# headstage.net
KiCad netlist of a schematic drawn in EAGLE
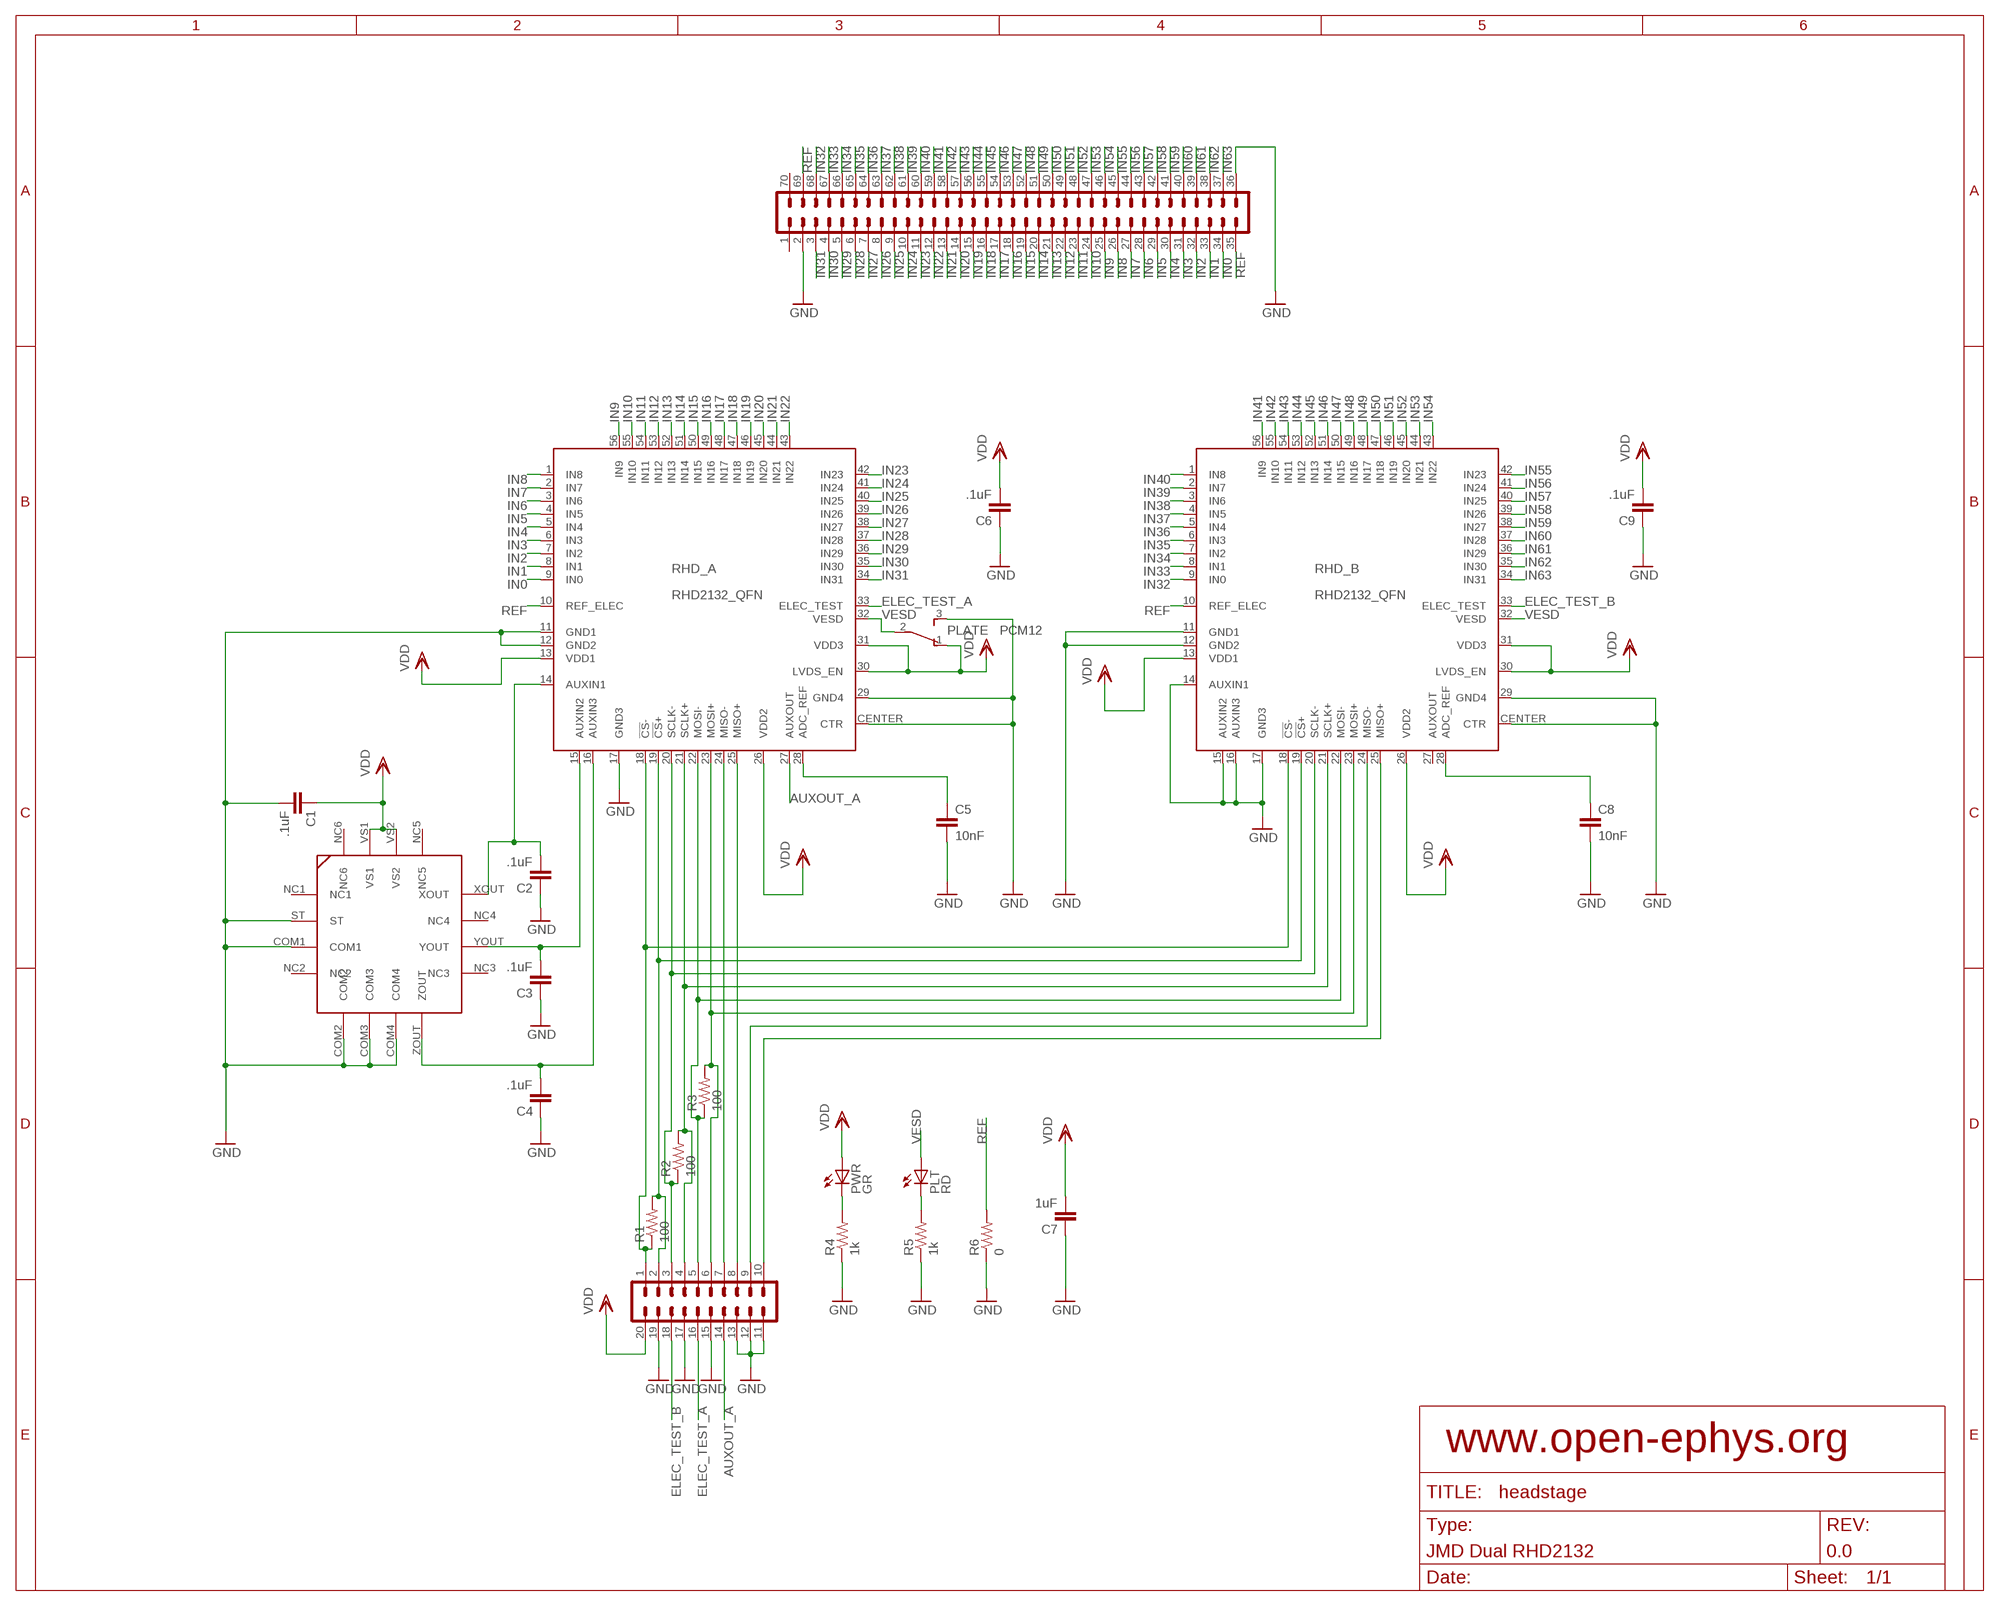
[diagram p0: schematic, sheet 1]

(export (version "E")
  (design (tool "Eeschema 10.0.6"))
  (components
    (comp (ref "AIN")
      (value "JMD70")
      (footprint "eagle-import:JMD70")
      (libsource (lib "eagle-import") (part "PINHD-2X35_JMD70"))
    )
    (comp (ref "C1")
      (value ".1uF")
      (footprint "eagle-import:0402")
      (libsource (lib "eagle-import") (part "C_0402"))
    )
    (comp (ref "C2")
      (value ".1uF")
      (footprint "eagle-import:0402")
      (libsource (lib "eagle-import") (part "C_0402"))
    )
    (comp (ref "C3")
      (value ".1uF")
      (footprint "eagle-import:0402")
      (libsource (lib "eagle-import") (part "C_0402"))
    )
    (comp (ref "C4")
      (value ".1uF")
      (footprint "eagle-import:0402")
      (libsource (lib "eagle-import") (part "C_0402"))
    )
    (comp (ref "C5")
      (value "10nF")
      (footprint "eagle-import:0402")
      (libsource (lib "eagle-import") (part "C_0402"))
    )
    (comp (ref "C6")
      (value ".1uF")
      (footprint "eagle-import:0603")
      (libsource (lib "eagle-import") (part "C_0603"))
    )
    (comp (ref "C7")
      (value "1uF")
      (footprint "eagle-import:0603")
      (libsource (lib "eagle-import") (part "C_0603"))
    )
    (comp (ref "C8")
      (value "10nF")
      (footprint "eagle-import:0402")
      (libsource (lib "eagle-import") (part "C_0402"))
    )
    (comp (ref "C9")
      (value ".1uF")
      (footprint "eagle-import:0603")
      (libsource (lib "eagle-import") (part "C_0603"))
    )
    (comp (ref "OUT")
      (value "JMD")
      (footprint "eagle-import:JMD20-RA")
      (libsource (lib "eagle-import") (part "PINHD-2X10_JMD-RA"))
    )
    (comp (ref "PLATE")
      (value "PCM12")
      (footprint "eagle-import:PCM12")
      (libsource (lib "eagle-import") (part "SPDT_PCM12"))
    )
    (comp (ref "PLT")
      (value "RD")
      (footprint "eagle-import:CHIP-LED0603")
      (libsource (lib "eagle-import") (part "LED_0603"))
    )
    (comp (ref "PWR")
      (value "GR")
      (footprint "eagle-import:CHIP-LED0603")
      (libsource (lib "eagle-import") (part "LED_0603"))
    )
    (comp (ref "R1")
      (value "100")
      (footprint "eagle-import:0402")
      (libsource (lib "eagle-import") (part "R_0402"))
    )
    (comp (ref "R2")
      (value "100")
      (footprint "eagle-import:0402")
      (libsource (lib "eagle-import") (part "R_0402"))
    )
    (comp (ref "R3")
      (value "100")
      (footprint "eagle-import:0402")
      (libsource (lib "eagle-import") (part "R_0402"))
    )
    (comp (ref "R4")
      (value "1k")
      (footprint "eagle-import:0402")
      (libsource (lib "eagle-import") (part "R_0402"))
    )
    (comp (ref "R5")
      (value "1k")
      (footprint "eagle-import:0402")
      (libsource (lib "eagle-import") (part "R_0402"))
    )
    (comp (ref "R6")
      (value "0")
      (footprint "eagle-import:0402")
      (libsource (lib "eagle-import") (part "R_0402"))
    )
    (comp (ref "RHD_A")
      (value "RHD2132_QFN")
      (footprint "eagle-import:QFN56_8_X_8_LARGE")
      (libsource (lib "eagle-import") (part "RHD2132_QFN"))
    )
    (comp (ref "RHD_B")
      (value "RHD2132_QFN")
      (footprint "eagle-import:QFN56_8_X_8_LARGE")
      (libsource (lib "eagle-import") (part "RHD2132_QFN"))
    )
    (comp (ref "U1")
      (value "ADXL335")
      (footprint "eagle-import:ADXL335")
      (libsource (lib "eagle-import") (part "ADXL335"))
    )
  )
  (nets
    (net (code "1") (name "/AUXOUT_A") (class "Default")
      (node (ref "OUT") (pin "14") (pinfunction "14_14") (pintype "bidirectional"))
      (node (ref "RHD_A") (pin "27") (pinfunction "AUXOUT_27") (pintype "tri_state"))
    )
    (net (code "2") (name "/ELEC_TEST_A") (class "Default")
      (node (ref "OUT") (pin "16") (pinfunction "16_16") (pintype "bidirectional"))
      (node (ref "RHD_A") (pin "33") (pinfunction "ELEC_TEST_33") (pintype "input"))
    )
    (net (code "3") (name "/ELEC_TEST_B") (class "Default")
      (node (ref "OUT") (pin "18") (pinfunction "18_18") (pintype "bidirectional"))
      (node (ref "RHD_B") (pin "33") (pinfunction "ELEC_TEST_33") (pintype "input"))
    )
    (net (code "4") (name "/IN0") (class "Default")
      (node (ref "AIN") (pin "34") (pinfunction "34_34") (pintype "bidirectional"))
      (node (ref "RHD_A") (pin "9") (pinfunction "IN0_9") (pintype "input"))
    )
    (net (code "5") (name "/IN1") (class "Default")
      (node (ref "AIN") (pin "33") (pinfunction "33_33") (pintype "bidirectional"))
      (node (ref "RHD_A") (pin "8") (pinfunction "IN1_8") (pintype "input"))
    )
    (net (code "6") (name "/IN2") (class "Default")
      (node (ref "AIN") (pin "32") (pinfunction "32_32") (pintype "bidirectional"))
      (node (ref "RHD_A") (pin "7") (pinfunction "IN2_7") (pintype "input"))
    )
    (net (code "7") (name "/IN3") (class "Default")
      (node (ref "AIN") (pin "31") (pinfunction "31_31") (pintype "bidirectional"))
      (node (ref "RHD_A") (pin "6") (pinfunction "IN3_6") (pintype "input"))
    )
    (net (code "8") (name "/IN4") (class "Default")
      (node (ref "AIN") (pin "30") (pinfunction "30_30") (pintype "bidirectional"))
      (node (ref "RHD_A") (pin "5") (pinfunction "IN4_5") (pintype "input"))
    )
    (net (code "9") (name "/IN5") (class "Default")
      (node (ref "AIN") (pin "29") (pinfunction "29_29") (pintype "bidirectional"))
      (node (ref "RHD_A") (pin "4") (pinfunction "IN5_4") (pintype "input"))
    )
    (net (code "10") (name "/IN6") (class "Default")
      (node (ref "AIN") (pin "28") (pinfunction "28_28") (pintype "bidirectional"))
      (node (ref "RHD_A") (pin "3") (pinfunction "IN6_3") (pintype "input"))
    )
    (net (code "11") (name "/IN7") (class "Default")
      (node (ref "AIN") (pin "27") (pinfunction "27_27") (pintype "bidirectional"))
      (node (ref "RHD_A") (pin "2") (pinfunction "IN7_2") (pintype "input"))
    )
    (net (code "12") (name "/IN8") (class "Default")
      (node (ref "AIN") (pin "26") (pinfunction "26_26") (pintype "bidirectional"))
      (node (ref "RHD_A") (pin "1") (pinfunction "IN8_1") (pintype "input"))
    )
    (net (code "13") (name "/IN9") (class "Default")
      (node (ref "AIN") (pin "25") (pinfunction "25_25") (pintype "bidirectional"))
      (node (ref "RHD_A") (pin "56") (pinfunction "IN9_56") (pintype "input"))
    )
    (net (code "14") (name "/IN10") (class "Default")
      (node (ref "AIN") (pin "24") (pinfunction "24_24") (pintype "bidirectional"))
      (node (ref "RHD_A") (pin "55") (pinfunction "IN10_55") (pintype "input"))
    )
    (net (code "15") (name "/IN11") (class "Default")
      (node (ref "AIN") (pin "23") (pinfunction "23_23") (pintype "bidirectional"))
      (node (ref "RHD_A") (pin "54") (pinfunction "IN11_54") (pintype "input"))
    )
    (net (code "16") (name "/IN12") (class "Default")
      (node (ref "AIN") (pin "22") (pinfunction "22_22") (pintype "bidirectional"))
      (node (ref "RHD_A") (pin "53") (pinfunction "IN12_53") (pintype "input"))
    )
    (net (code "17") (name "/IN13") (class "Default")
      (node (ref "AIN") (pin "21") (pinfunction "21_21") (pintype "bidirectional"))
      (node (ref "RHD_A") (pin "52") (pinfunction "IN13_52") (pintype "input"))
    )
    (net (code "18") (name "/IN14") (class "Default")
      (node (ref "AIN") (pin "20") (pinfunction "20_20") (pintype "bidirectional"))
      (node (ref "RHD_A") (pin "51") (pinfunction "IN14_51") (pintype "input"))
    )
    (net (code "19") (name "/IN15") (class "Default")
      (node (ref "AIN") (pin "19") (pinfunction "19_19") (pintype "bidirectional"))
      (node (ref "RHD_A") (pin "50") (pinfunction "IN15_50") (pintype "input"))
    )
    (net (code "20") (name "/IN16") (class "Default")
      (node (ref "AIN") (pin "18") (pinfunction "18_18") (pintype "bidirectional"))
      (node (ref "RHD_A") (pin "49") (pinfunction "IN16_49") (pintype "input"))
    )
    (net (code "21") (name "/IN17") (class "Default")
      (node (ref "AIN") (pin "17") (pinfunction "17_17") (pintype "bidirectional"))
      (node (ref "RHD_A") (pin "48") (pinfunction "IN17_48") (pintype "input"))
    )
    (net (code "22") (name "/IN18") (class "Default")
      (node (ref "AIN") (pin "16") (pinfunction "16_16") (pintype "bidirectional"))
      (node (ref "RHD_A") (pin "47") (pinfunction "IN18_47") (pintype "input"))
    )
    (net (code "23") (name "/IN19") (class "Default")
      (node (ref "AIN") (pin "15") (pinfunction "15_15") (pintype "bidirectional"))
      (node (ref "RHD_A") (pin "46") (pinfunction "IN19_46") (pintype "input"))
    )
    (net (code "24") (name "/IN20") (class "Default")
      (node (ref "AIN") (pin "14") (pinfunction "14_14") (pintype "bidirectional"))
      (node (ref "RHD_A") (pin "45") (pinfunction "IN20_45") (pintype "input"))
    )
    (net (code "25") (name "/IN21") (class "Default")
      (node (ref "AIN") (pin "13") (pinfunction "13_13") (pintype "bidirectional"))
      (node (ref "RHD_A") (pin "44") (pinfunction "IN21_44") (pintype "input"))
    )
    (net (code "26") (name "/IN22") (class "Default")
      (node (ref "AIN") (pin "12") (pinfunction "12_12") (pintype "bidirectional"))
      (node (ref "RHD_A") (pin "43") (pinfunction "IN22_43") (pintype "input"))
    )
    (net (code "27") (name "/IN23") (class "Default")
      (node (ref "AIN") (pin "11") (pinfunction "11_11") (pintype "bidirectional"))
      (node (ref "RHD_A") (pin "42") (pinfunction "IN23_42") (pintype "input"))
    )
    (net (code "28") (name "/IN24") (class "Default")
      (node (ref "AIN") (pin "10") (pinfunction "10_10") (pintype "bidirectional"))
      (node (ref "RHD_A") (pin "41") (pinfunction "IN24_41") (pintype "input"))
    )
    (net (code "29") (name "/IN25") (class "Default")
      (node (ref "AIN") (pin "9") (pinfunction "9_9") (pintype "bidirectional"))
      (node (ref "RHD_A") (pin "40") (pinfunction "IN25_40") (pintype "input"))
    )
    (net (code "30") (name "/IN26") (class "Default")
      (node (ref "AIN") (pin "8") (pinfunction "8_8") (pintype "bidirectional"))
      (node (ref "RHD_A") (pin "39") (pinfunction "IN26_39") (pintype "input"))
    )
    (net (code "31") (name "/IN27") (class "Default")
      (node (ref "AIN") (pin "7") (pinfunction "7_7") (pintype "bidirectional"))
      (node (ref "RHD_A") (pin "38") (pinfunction "IN27_38") (pintype "input"))
    )
    (net (code "32") (name "/IN28") (class "Default")
      (node (ref "AIN") (pin "6") (pinfunction "6_6") (pintype "bidirectional"))
      (node (ref "RHD_A") (pin "37") (pinfunction "IN28_37") (pintype "input"))
    )
    (net (code "33") (name "/IN29") (class "Default")
      (node (ref "AIN") (pin "5") (pinfunction "5_5") (pintype "bidirectional"))
      (node (ref "RHD_A") (pin "36") (pinfunction "IN29_36") (pintype "input"))
    )
    (net (code "34") (name "/IN30") (class "Default")
      (node (ref "AIN") (pin "4") (pinfunction "4_4") (pintype "bidirectional"))
      (node (ref "RHD_A") (pin "35") (pinfunction "IN30_35") (pintype "input"))
    )
    (net (code "35") (name "/IN31") (class "Default")
      (node (ref "AIN") (pin "3") (pinfunction "3_3") (pintype "bidirectional"))
      (node (ref "RHD_A") (pin "34") (pinfunction "IN31_34") (pintype "input"))
    )
    (net (code "36") (name "/IN32") (class "Default")
      (node (ref "AIN") (pin "68") (pinfunction "68_68") (pintype "bidirectional"))
      (node (ref "RHD_B") (pin "9") (pinfunction "IN0_9") (pintype "input"))
    )
    (net (code "37") (name "/IN33") (class "Default")
      (node (ref "AIN") (pin "67") (pinfunction "67_67") (pintype "bidirectional"))
      (node (ref "RHD_B") (pin "8") (pinfunction "IN1_8") (pintype "input"))
    )
    (net (code "38") (name "/IN34") (class "Default")
      (node (ref "AIN") (pin "66") (pinfunction "66_66") (pintype "bidirectional"))
      (node (ref "RHD_B") (pin "7") (pinfunction "IN2_7") (pintype "input"))
    )
    (net (code "39") (name "/IN35") (class "Default")
      (node (ref "AIN") (pin "65") (pinfunction "65_65") (pintype "bidirectional"))
      (node (ref "RHD_B") (pin "6") (pinfunction "IN3_6") (pintype "input"))
    )
    (net (code "40") (name "/IN36") (class "Default")
      (node (ref "AIN") (pin "64") (pinfunction "64_64") (pintype "bidirectional"))
      (node (ref "RHD_B") (pin "5") (pinfunction "IN4_5") (pintype "input"))
    )
    (net (code "41") (name "/IN37") (class "Default")
      (node (ref "AIN") (pin "63") (pinfunction "63_63") (pintype "bidirectional"))
      (node (ref "RHD_B") (pin "4") (pinfunction "IN5_4") (pintype "input"))
    )
    (net (code "42") (name "/IN38") (class "Default")
      (node (ref "AIN") (pin "62") (pinfunction "62_62") (pintype "bidirectional"))
      (node (ref "RHD_B") (pin "3") (pinfunction "IN6_3") (pintype "input"))
    )
    (net (code "43") (name "/IN39") (class "Default")
      (node (ref "AIN") (pin "61") (pinfunction "61_61") (pintype "bidirectional"))
      (node (ref "RHD_B") (pin "2") (pinfunction "IN7_2") (pintype "input"))
    )
    (net (code "44") (name "/IN40") (class "Default")
      (node (ref "AIN") (pin "60") (pinfunction "60_60") (pintype "bidirectional"))
      (node (ref "RHD_B") (pin "1") (pinfunction "IN8_1") (pintype "input"))
    )
    (net (code "45") (name "/IN41") (class "Default")
      (node (ref "AIN") (pin "59") (pinfunction "59_59") (pintype "bidirectional"))
      (node (ref "RHD_B") (pin "56") (pinfunction "IN9_56") (pintype "input"))
    )
    (net (code "46") (name "/IN42") (class "Default")
      (node (ref "AIN") (pin "58") (pinfunction "58_58") (pintype "bidirectional"))
      (node (ref "RHD_B") (pin "55") (pinfunction "IN10_55") (pintype "input"))
    )
    (net (code "47") (name "/IN43") (class "Default")
      (node (ref "AIN") (pin "57") (pinfunction "57_57") (pintype "bidirectional"))
      (node (ref "RHD_B") (pin "54") (pinfunction "IN11_54") (pintype "input"))
    )
    (net (code "48") (name "/IN44") (class "Default")
      (node (ref "AIN") (pin "56") (pinfunction "56_56") (pintype "bidirectional"))
      (node (ref "RHD_B") (pin "53") (pinfunction "IN12_53") (pintype "input"))
    )
    (net (code "49") (name "/IN45") (class "Default")
      (node (ref "AIN") (pin "55") (pinfunction "55_55") (pintype "bidirectional"))
      (node (ref "RHD_B") (pin "52") (pinfunction "IN13_52") (pintype "input"))
    )
    (net (code "50") (name "/IN46") (class "Default")
      (node (ref "AIN") (pin "54") (pinfunction "54_54") (pintype "bidirectional"))
      (node (ref "RHD_B") (pin "51") (pinfunction "IN14_51") (pintype "input"))
    )
    (net (code "51") (name "/IN47") (class "Default")
      (node (ref "AIN") (pin "53") (pinfunction "53_53") (pintype "bidirectional"))
      (node (ref "RHD_B") (pin "50") (pinfunction "IN15_50") (pintype "input"))
    )
    (net (code "52") (name "/IN48") (class "Default")
      (node (ref "AIN") (pin "52") (pinfunction "52_52") (pintype "bidirectional"))
      (node (ref "RHD_B") (pin "49") (pinfunction "IN16_49") (pintype "input"))
    )
    (net (code "53") (name "/IN49") (class "Default")
      (node (ref "AIN") (pin "51") (pinfunction "51_51") (pintype "bidirectional"))
      (node (ref "RHD_B") (pin "48") (pinfunction "IN17_48") (pintype "input"))
    )
    (net (code "54") (name "/IN50") (class "Default")
      (node (ref "AIN") (pin "50") (pinfunction "50_50") (pintype "bidirectional"))
      (node (ref "RHD_B") (pin "47") (pinfunction "IN18_47") (pintype "input"))
    )
    (net (code "55") (name "/IN51") (class "Default")
      (node (ref "AIN") (pin "49") (pinfunction "49_49") (pintype "bidirectional"))
      (node (ref "RHD_B") (pin "46") (pinfunction "IN19_46") (pintype "input"))
    )
    (net (code "56") (name "/IN52") (class "Default")
      (node (ref "AIN") (pin "48") (pinfunction "48_48") (pintype "bidirectional"))
      (node (ref "RHD_B") (pin "45") (pinfunction "IN20_45") (pintype "input"))
    )
    (net (code "57") (name "/IN53") (class "Default")
      (node (ref "AIN") (pin "47") (pinfunction "47_47") (pintype "bidirectional"))
      (node (ref "RHD_B") (pin "44") (pinfunction "IN21_44") (pintype "input"))
    )
    (net (code "58") (name "/IN54") (class "Default")
      (node (ref "AIN") (pin "46") (pinfunction "46_46") (pintype "bidirectional"))
      (node (ref "RHD_B") (pin "43") (pinfunction "IN22_43") (pintype "input"))
    )
    (net (code "59") (name "/IN55") (class "Default")
      (node (ref "AIN") (pin "45") (pinfunction "45_45") (pintype "bidirectional"))
      (node (ref "RHD_B") (pin "42") (pinfunction "IN23_42") (pintype "input"))
    )
    (net (code "60") (name "/IN56") (class "Default")
      (node (ref "AIN") (pin "44") (pinfunction "44_44") (pintype "bidirectional"))
      (node (ref "RHD_B") (pin "41") (pinfunction "IN24_41") (pintype "input"))
    )
    (net (code "61") (name "/IN57") (class "Default")
      (node (ref "AIN") (pin "43") (pinfunction "43_43") (pintype "bidirectional"))
      (node (ref "RHD_B") (pin "40") (pinfunction "IN25_40") (pintype "input"))
    )
    (net (code "62") (name "/IN58") (class "Default")
      (node (ref "AIN") (pin "42") (pinfunction "42_42") (pintype "bidirectional"))
      (node (ref "RHD_B") (pin "39") (pinfunction "IN26_39") (pintype "input"))
    )
    (net (code "63") (name "/IN59") (class "Default")
      (node (ref "AIN") (pin "41") (pinfunction "41_41") (pintype "bidirectional"))
      (node (ref "RHD_B") (pin "38") (pinfunction "IN27_38") (pintype "input"))
    )
    (net (code "64") (name "/IN60") (class "Default")
      (node (ref "AIN") (pin "40") (pinfunction "40_40") (pintype "bidirectional"))
      (node (ref "RHD_B") (pin "37") (pinfunction "IN28_37") (pintype "input"))
    )
    (net (code "65") (name "/IN61") (class "Default")
      (node (ref "AIN") (pin "39") (pinfunction "39_39") (pintype "bidirectional"))
      (node (ref "RHD_B") (pin "36") (pinfunction "IN29_36") (pintype "input"))
    )
    (net (code "66") (name "/IN62") (class "Default")
      (node (ref "AIN") (pin "38") (pinfunction "38_38") (pintype "bidirectional"))
      (node (ref "RHD_B") (pin "35") (pinfunction "IN30_35") (pintype "input"))
    )
    (net (code "67") (name "/IN63") (class "Default")
      (node (ref "AIN") (pin "37") (pinfunction "37_37") (pintype "bidirectional"))
      (node (ref "RHD_B") (pin "34") (pinfunction "IN31_34") (pintype "input"))
    )
    (net (code "68") (name "/REF") (class "Default")
      (node (ref "AIN") (pin "35") (pinfunction "35_35") (pintype "bidirectional"))
      (node (ref "AIN") (pin "69") (pinfunction "69_69") (pintype "bidirectional"))
      (node (ref "R6") (pin "2") (pinfunction "2_2") (pintype "passive"))
      (node (ref "RHD_A") (pin "10") (pinfunction "REF_ELEC_10") (pintype "input"))
      (node (ref "RHD_B") (pin "10") (pinfunction "REF_ELEC_10") (pintype "input"))
    )
    (net (code "69") (name "/VESD") (class "Default")
      (node (ref "PLATE") (pin "2") (pinfunction "2_2") (pintype "passive"))
      (node (ref "PLT") (pin "A") (pinfunction "A_A") (pintype "passive"))
      (node (ref "RHD_A") (pin "32") (pinfunction "VESD_32") (pintype "power_in"))
      (node (ref "RHD_B") (pin "32") (pinfunction "VESD_32") (pintype "power_in"))
    )
    (net (code "70") (name "GND") (class "Default")
      (node (ref "AIN") (pin "2") (pinfunction "2_2") (pintype "bidirectional"))
      (node (ref "AIN") (pin "36") (pinfunction "36_36") (pintype "bidirectional"))
      (node (ref "C1") (pin "2") (pinfunction "2_2") (pintype "passive"))
      (node (ref "C2") (pin "1") (pinfunction "1_1") (pintype "passive"))
      (node (ref "C3") (pin "1") (pinfunction "1_1") (pintype "passive"))
      (node (ref "C4") (pin "1") (pinfunction "1_1") (pintype "passive"))
      (node (ref "C5") (pin "2") (pinfunction "2_2") (pintype "passive"))
      (node (ref "C6") (pin "1") (pinfunction "1_1") (pintype "passive"))
      (node (ref "C7") (pin "1") (pinfunction "1_1") (pintype "passive"))
      (node (ref "C8") (pin "2") (pinfunction "2_2") (pintype "passive"))
      (node (ref "C9") (pin "1") (pinfunction "1_1") (pintype "passive"))
      (node (ref "OUT") (pin "11") (pinfunction "11_11") (pintype "bidirectional"))
      (node (ref "OUT") (pin "12") (pinfunction "12_12") (pintype "bidirectional"))
      (node (ref "OUT") (pin "13") (pinfunction "13_13") (pintype "bidirectional"))
      (node (ref "OUT") (pin "15") (pinfunction "15_15") (pintype "bidirectional"))
      (node (ref "OUT") (pin "17") (pinfunction "17_17") (pintype "bidirectional"))
      (node (ref "OUT") (pin "19") (pinfunction "19_19") (pintype "bidirectional"))
      (node (ref "PLATE") (pin "3") (pinfunction "3_3") (pintype "passive"))
      (node (ref "R4") (pin "1") (pinfunction "1_1") (pintype "passive"))
      (node (ref "R5") (pin "1") (pinfunction "1_1") (pintype "passive"))
      (node (ref "R6") (pin "1") (pinfunction "1_1") (pintype "passive"))
      (node (ref "RHD_A") (pin "11") (pinfunction "GND1_11") (pintype "power_in"))
      (node (ref "RHD_A") (pin "12") (pinfunction "GND2_12") (pintype "power_in"))
      (node (ref "RHD_A") (pin "17") (pinfunction "GND3_17") (pintype "power_in"))
      (node (ref "RHD_A") (pin "29") (pinfunction "GND4_29") (pintype "power_in"))
      (node (ref "RHD_A") (pin "CENTER") (pinfunction "CTR_CENTER") (pintype "power_in"))
      (node (ref "RHD_B") (pin "11") (pinfunction "GND1_11") (pintype "power_in"))
      (node (ref "RHD_B") (pin "12") (pinfunction "GND2_12") (pintype "power_in"))
      (node (ref "RHD_B") (pin "14") (pinfunction "AUXIN1_14") (pintype "input"))
      (node (ref "RHD_B") (pin "15") (pinfunction "AUXIN2_15") (pintype "input"))
      (node (ref "RHD_B") (pin "16") (pinfunction "AUXIN3_16") (pintype "input"))
      (node (ref "RHD_B") (pin "17") (pinfunction "GND3_17") (pintype "power_in"))
      (node (ref "RHD_B") (pin "29") (pinfunction "GND4_29") (pintype "power_in"))
      (node (ref "RHD_B") (pin "CENTER") (pinfunction "CTR_CENTER") (pintype "power_in"))
      (node (ref "U1") (pin "COM1") (pinfunction "COM1_COM1") (pintype "bidirectional"))
      (node (ref "U1") (pin "COM2") (pinfunction "COM2_COM2") (pintype "bidirectional"))
      (node (ref "U1") (pin "COM3") (pinfunction "COM3_COM3") (pintype "bidirectional"))
      (node (ref "U1") (pin "COM4") (pinfunction "COM4_COM4") (pintype "bidirectional"))
      (node (ref "U1") (pin "ST") (pinfunction "ST_ST") (pintype "bidirectional"))
    )
    (net (code "71") (name "Net-(PLT-PadC)") (class "Default")
      (node (ref "PLT") (pin "C") (pinfunction "C_C") (pintype "passive"))
      (node (ref "R5") (pin "2") (pinfunction "2_2") (pintype "passive"))
    )
    (net (code "72") (name "Net-(PWR-PadC)") (class "Default")
      (node (ref "PWR") (pin "C") (pinfunction "C_C") (pintype "passive"))
      (node (ref "R4") (pin "2") (pinfunction "2_2") (pintype "passive"))
    )
    (net (code "73") (name "Net-(RHD_A-ADC_REF)") (class "Default")
      (node (ref "C5") (pin "1") (pinfunction "1_1") (pintype "passive"))
      (node (ref "RHD_A") (pin "28") (pinfunction "ADC_REF_28") (pintype "passive"))
    )
    (net (code "74") (name "Net-(RHD_A-AUXIN1)") (class "Default")
      (node (ref "C2") (pin "2") (pinfunction "2_2") (pintype "passive"))
      (node (ref "RHD_A") (pin "14") (pinfunction "AUXIN1_14") (pintype "input"))
      (node (ref "U1") (pin "XOUT") (pinfunction "XOUT_XOUT") (pintype "bidirectional"))
    )
    (net (code "75") (name "Net-(RHD_A-AUXIN2)") (class "Default")
      (node (ref "C3") (pin "2") (pinfunction "2_2") (pintype "passive"))
      (node (ref "RHD_A") (pin "15") (pinfunction "AUXIN2_15") (pintype "input"))
      (node (ref "U1") (pin "YOUT") (pinfunction "YOUT_YOUT") (pintype "bidirectional"))
    )
    (net (code "76") (name "Net-(RHD_A-AUXIN3)") (class "Default")
      (node (ref "C4") (pin "2") (pinfunction "2_2") (pintype "passive"))
      (node (ref "RHD_A") (pin "16") (pinfunction "AUXIN3_16") (pintype "input"))
      (node (ref "U1") (pin "ZOUT") (pinfunction "ZOUT_ZOUT") (pintype "bidirectional"))
    )
    (net (code "77") (name "Net-(RHD_A-MISO+)") (class "Default")
      (node (ref "OUT") (pin "8") (pinfunction "8_8") (pintype "bidirectional"))
      (node (ref "RHD_A") (pin "25") (pinfunction "MISO+_25") (pintype "output"))
    )
    (net (code "78") (name "Net-(RHD_A-MISO-)") (class "Default")
      (node (ref "OUT") (pin "7") (pinfunction "7_7") (pintype "bidirectional"))
      (node (ref "RHD_A") (pin "24") (pinfunction "MISO-_24") (pintype "output"))
    )
    (net (code "79") (name "Net-(RHD_A-MOSI+)") (class "Default")
      (node (ref "OUT") (pin "6") (pinfunction "6_6") (pintype "bidirectional"))
      (node (ref "R3") (pin "2") (pinfunction "2_2") (pintype "passive"))
      (node (ref "RHD_A") (pin "23") (pinfunction "MOSI+_23") (pintype "input"))
      (node (ref "RHD_B") (pin "23") (pinfunction "MOSI+_23") (pintype "input"))
    )
    (net (code "80") (name "Net-(RHD_A-MOSI-)") (class "Default")
      (node (ref "OUT") (pin "5") (pinfunction "5_5") (pintype "bidirectional"))
      (node (ref "R3") (pin "1") (pinfunction "1_1") (pintype "passive"))
      (node (ref "RHD_A") (pin "22") (pinfunction "MOSI-_22") (pintype "input"))
      (node (ref "RHD_B") (pin "22") (pinfunction "MOSI-_22") (pintype "input"))
    )
    (net (code "81") (name "Net-(RHD_A-SCLK+)") (class "Default")
      (node (ref "OUT") (pin "4") (pinfunction "4_4") (pintype "bidirectional"))
      (node (ref "R2") (pin "2") (pinfunction "2_2") (pintype "passive"))
      (node (ref "RHD_A") (pin "21") (pinfunction "SCLK+_21") (pintype "input"))
      (node (ref "RHD_B") (pin "21") (pinfunction "SCLK+_21") (pintype "input"))
    )
    (net (code "82") (name "Net-(RHD_A-SCLK-)") (class "Default")
      (node (ref "OUT") (pin "3") (pinfunction "3_3") (pintype "bidirectional"))
      (node (ref "R2") (pin "1") (pinfunction "1_1") (pintype "passive"))
      (node (ref "RHD_A") (pin "20") (pinfunction "SCLK-_20") (pintype "input"))
      (node (ref "RHD_B") (pin "20") (pinfunction "SCLK-_20") (pintype "input"))
    )
    (net (code "83") (name "Net-(RHD_A-~{CS}+)") (class "Default")
      (node (ref "OUT") (pin "2") (pinfunction "2_2") (pintype "bidirectional"))
      (node (ref "R1") (pin "2") (pinfunction "2_2") (pintype "passive"))
      (node (ref "RHD_A") (pin "19") (pinfunction "~{CS}+_19") (pintype "input"))
      (node (ref "RHD_B") (pin "19") (pinfunction "~{CS}+_19") (pintype "input"))
    )
    (net (code "84") (name "Net-(RHD_A-~{CS}-)") (class "Default")
      (node (ref "OUT") (pin "1") (pinfunction "1_1") (pintype "bidirectional"))
      (node (ref "R1") (pin "1") (pinfunction "1_1") (pintype "passive"))
      (node (ref "RHD_A") (pin "18") (pinfunction "~{CS}-_18") (pintype "input"))
      (node (ref "RHD_B") (pin "18") (pinfunction "~{CS}-_18") (pintype "input"))
    )
    (net (code "85") (name "Net-(RHD_B-ADC_REF)") (class "Default")
      (node (ref "C8") (pin "1") (pinfunction "1_1") (pintype "passive"))
      (node (ref "RHD_B") (pin "28") (pinfunction "ADC_REF_28") (pintype "passive"))
    )
    (net (code "86") (name "Net-(RHD_B-MISO+)") (class "Default")
      (node (ref "OUT") (pin "10") (pinfunction "10_10") (pintype "bidirectional"))
      (node (ref "RHD_B") (pin "25") (pinfunction "MISO+_25") (pintype "output"))
    )
    (net (code "87") (name "Net-(RHD_B-MISO-)") (class "Default")
      (node (ref "OUT") (pin "9") (pinfunction "9_9") (pintype "bidirectional"))
      (node (ref "RHD_B") (pin "24") (pinfunction "MISO-_24") (pintype "output"))
    )
    (net (code "88") (name "VDD") (class "Default")
      (node (ref "C1") (pin "1") (pinfunction "1_1") (pintype "passive"))
      (node (ref "C6") (pin "2") (pinfunction "2_2") (pintype "passive"))
      (node (ref "C7") (pin "2") (pinfunction "2_2") (pintype "passive"))
      (node (ref "C9") (pin "2") (pinfunction "2_2") (pintype "passive"))
      (node (ref "OUT") (pin "20") (pinfunction "20_20") (pintype "bidirectional"))
      (node (ref "PLATE") (pin "1") (pinfunction "1_1") (pintype "passive"))
      (node (ref "PWR") (pin "A") (pinfunction "A_A") (pintype "passive"))
      (node (ref "RHD_A") (pin "13") (pinfunction "VDD1_13") (pintype "power_in"))
      (node (ref "RHD_A") (pin "26") (pinfunction "VDD2_26") (pintype "power_in"))
      (node (ref "RHD_A") (pin "30") (pinfunction "LVDS_EN_30") (pintype "input"))
      (node (ref "RHD_A") (pin "31") (pinfunction "VDD3_31") (pintype "power_in"))
      (node (ref "RHD_B") (pin "13") (pinfunction "VDD1_13") (pintype "power_in"))
      (node (ref "RHD_B") (pin "26") (pinfunction "VDD2_26") (pintype "power_in"))
      (node (ref "RHD_B") (pin "30") (pinfunction "LVDS_EN_30") (pintype "input"))
      (node (ref "RHD_B") (pin "31") (pinfunction "VDD3_31") (pintype "power_in"))
      (node (ref "U1") (pin "VS1") (pinfunction "VS1_VS1") (pintype "bidirectional"))
      (node (ref "U1") (pin "VS2") (pinfunction "VS2_VS2") (pintype "bidirectional"))
    )
    (net (code "89") (name "unconnected-(AIN-Pad1)") (class "Default")
      (node (ref "AIN") (pin "1") (pinfunction "1_1") (pintype "bidirectional"))
    )
    (net (code "90") (name "unconnected-(AIN-Pad70)") (class "Default")
      (node (ref "AIN") (pin "70") (pinfunction "70_70") (pintype "bidirectional"))
    )
    (net (code "91") (name "unconnected-(RHD_B-AUXOUT-Pad27)") (class "Default")
      (node (ref "RHD_B") (pin "27") (pinfunction "AUXOUT_27") (pintype "tri_state"))
    )
    (net (code "92") (name "unconnected-(U1-PadNC1)") (class "Default")
      (node (ref "U1") (pin "NC1") (pinfunction "NC1_NC1") (pintype "bidirectional"))
    )
    (net (code "93") (name "unconnected-(U1-PadNC2)") (class "Default")
      (node (ref "U1") (pin "NC2") (pinfunction "NC2_NC2") (pintype "bidirectional"))
    )
    (net (code "94") (name "unconnected-(U1-PadNC3)") (class "Default")
      (node (ref "U1") (pin "NC3") (pinfunction "NC3_NC3") (pintype "bidirectional"))
    )
    (net (code "95") (name "unconnected-(U1-PadNC4)") (class "Default")
      (node (ref "U1") (pin "NC4") (pinfunction "NC4_NC4") (pintype "bidirectional"))
    )
    (net (code "96") (name "unconnected-(U1-PadNC5)") (class "Default")
      (node (ref "U1") (pin "NC5") (pinfunction "NC5_NC5") (pintype "bidirectional"))
    )
    (net (code "97") (name "unconnected-(U1-PadNC6)") (class "Default")
      (node (ref "U1") (pin "NC6") (pinfunction "NC6_NC6") (pintype "bidirectional"))
    )
  )
)
